# addonv2.net
KiCad netlist of a schematic drawn in EAGLE
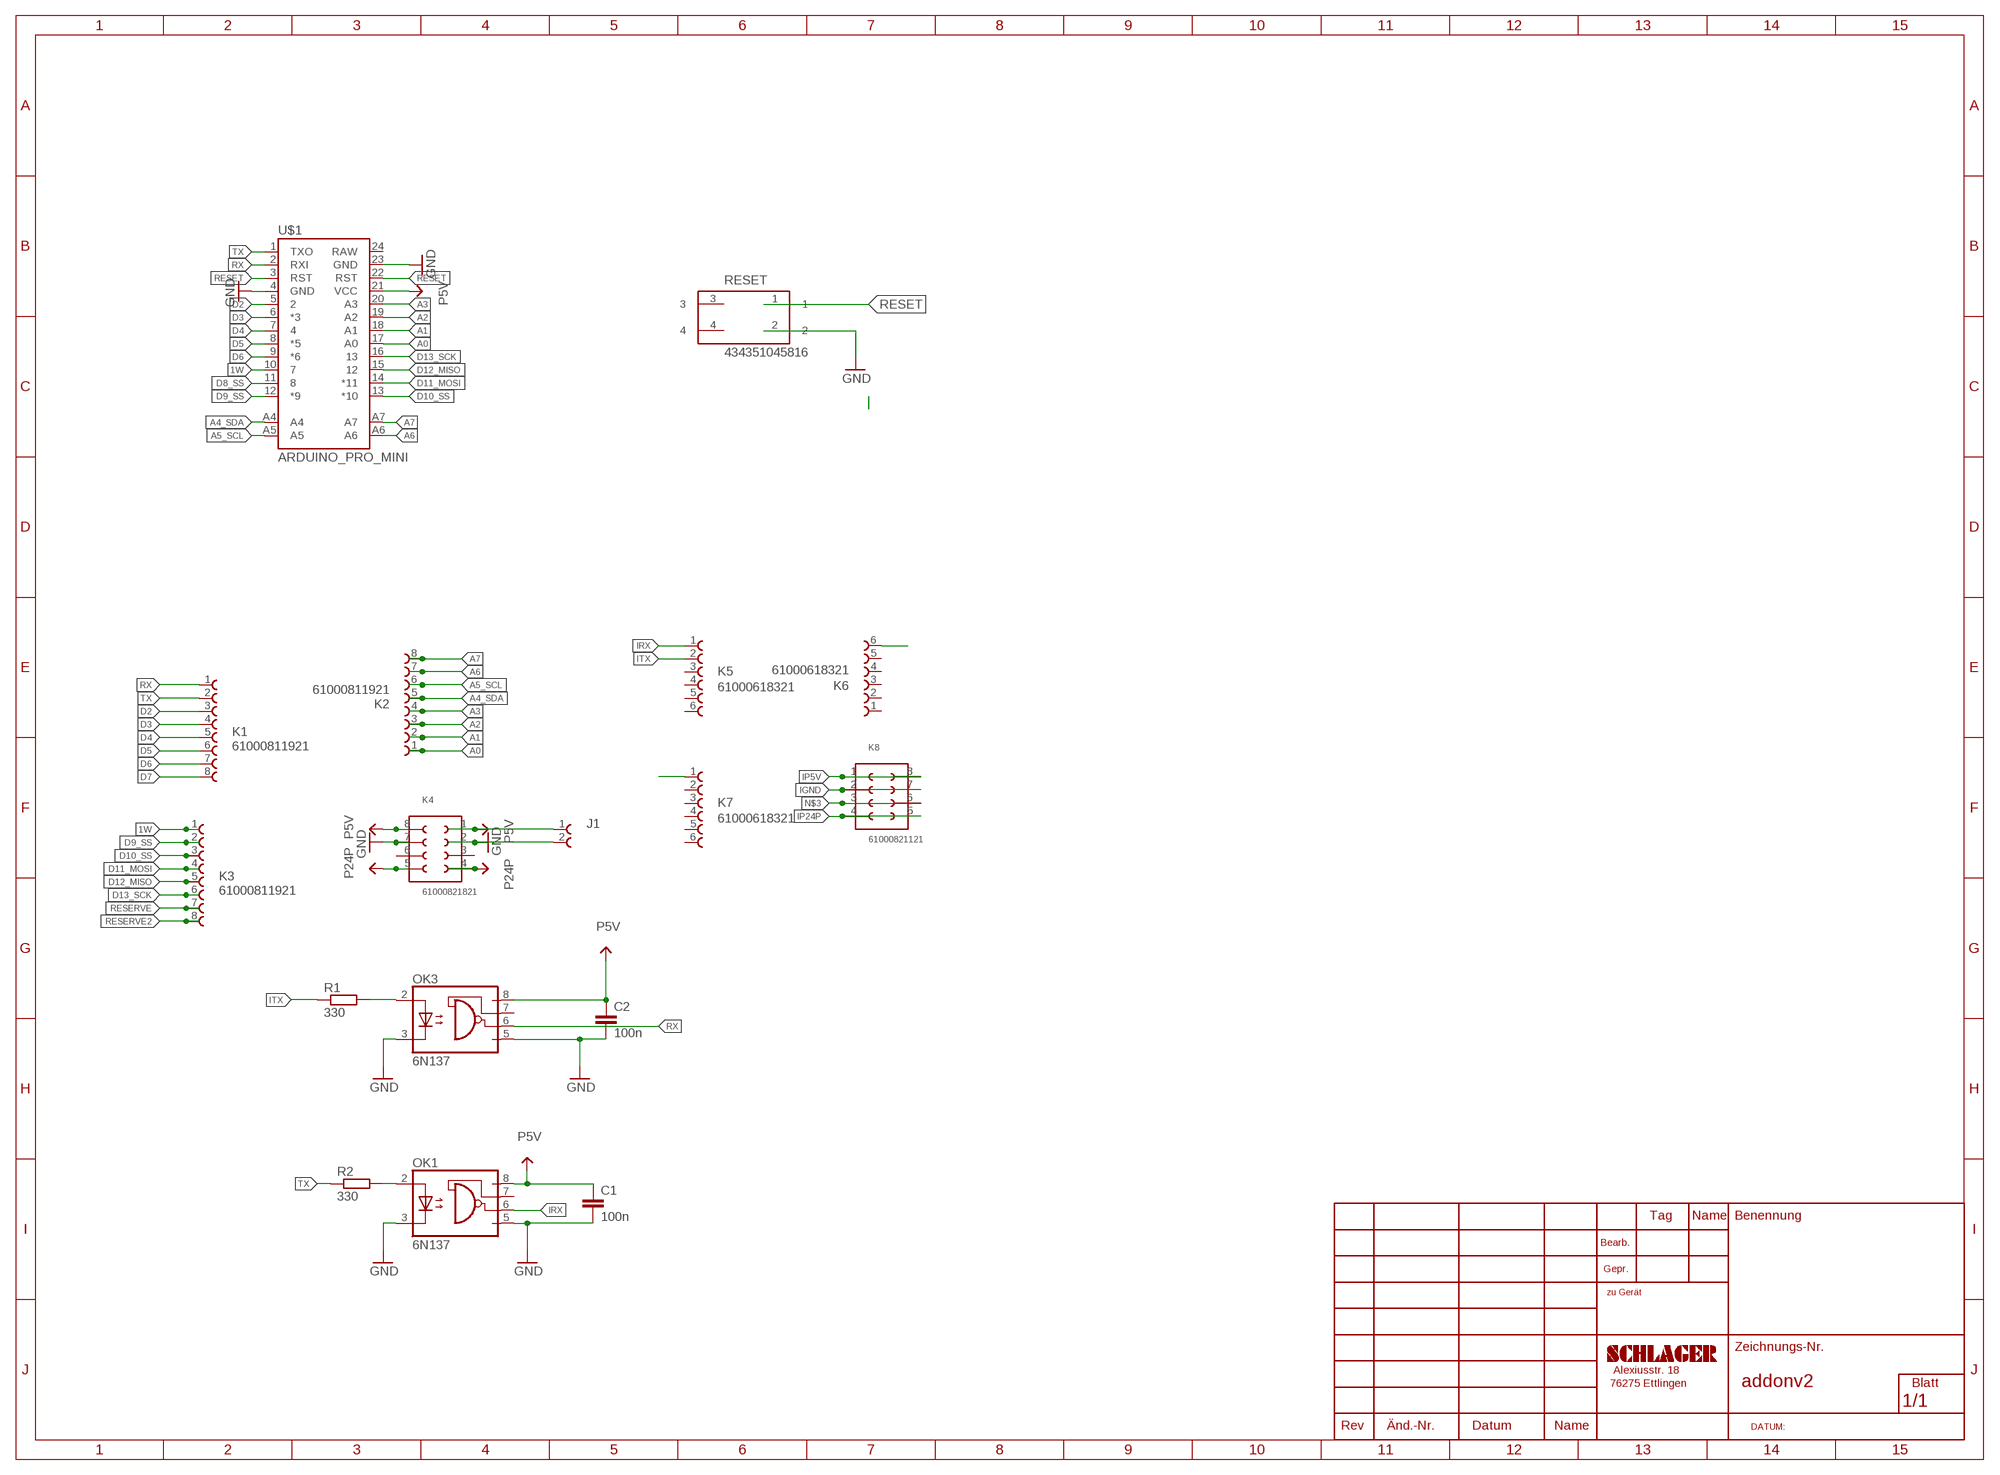
[diagram p0: schematic, sheet 1]

(export (version "E")
  (design (tool "Eeschema 10.0.6"))
  (components
    (comp (ref "C1")
      (value "100n")
      (footprint "eagle-import:C0805")
      (libsource (lib "eagle-import") (part "C-EUC0805"))
    )
    (comp (ref "C2")
      (value "100n")
      (footprint "eagle-import:C0805")
      (libsource (lib "eagle-import") (part "C-EUC0805"))
    )
    (comp (ref "J1")
      (value "691322310002")
      (footprint "eagle-import:691322310002")
      (libsource (lib "eagle-import") (part "691322310002"))
    )
    (comp (ref "K1")
      (value "61000811921")
      (footprint "eagle-import:61000811921")
      (libsource (lib "eagle-import") (part "61000811921"))
    )
    (comp (ref "K2")
      (value "61000811921")
      (footprint "eagle-import:61000811921")
      (libsource (lib "eagle-import") (part "61000811921"))
    )
    (comp (ref "K3")
      (value "61000811921")
      (footprint "eagle-import:61000811921")
      (libsource (lib "eagle-import") (part "61000811921"))
    )
    (comp (ref "K4")
      (value "61000821821")
      (footprint "eagle-import:61000821821")
      (libsource (lib "eagle-import") (part "61000821821"))
    )
    (comp (ref "K5")
      (value "61000618321")
      (footprint "eagle-import:61000618321")
      (libsource (lib "eagle-import") (part "61000618321"))
    )
    (comp (ref "K6")
      (value "61000618321")
      (footprint "eagle-import:61000618321")
      (libsource (lib "eagle-import") (part "61000618321"))
    )
    (comp (ref "K7")
      (value "61000618321")
      (footprint "eagle-import:61000618321")
      (libsource (lib "eagle-import") (part "61000618321"))
    )
    (comp (ref "K8")
      (value "61000821121")
      (footprint "eagle-import:61000821121")
      (libsource (lib "eagle-import") (part "61000821121"))
    )
    (comp (ref "OK1")
      (value "6N137")
      (footprint "eagle-import:DIL08")
      (libsource (lib "eagle-import") (part "6N137"))
    )
    (comp (ref "OK3")
      (value "6N137")
      (footprint "eagle-import:DIL08")
      (libsource (lib "eagle-import") (part "6N137"))
    )
    (comp (ref "R1")
      (value "330")
      (footprint "eagle-import:R0805")
      (libsource (lib "eagle-import") (part "R-EU_R0805"))
    )
    (comp (ref "R2")
      (value "330")
      (footprint "eagle-import:R0805")
      (libsource (lib "eagle-import") (part "R-EU_R0805"))
    )
    (comp (ref "RESET")
      (value "434351045816")
      (footprint "eagle-import:434351045816")
      (libsource (lib "eagle-import") (part "434351045816"))
    )
    (comp (ref "U$1")
      (value "ARDUINO_PRO_MINI")
      (footprint "eagle-import:ARDUINO_PRO_MINI")
      (libsource (lib "eagle-import") (part "ARDUINO_PRO_MINI"))
    )
  )
  (nets
    (net (code "1") (name "1W") (class "Default")
      (node (ref "K3") (pin "1") (pinfunction "1_1") (pintype "passive"))
      (node (ref "U$1") (pin "10") (pinfunction "7_10") (pintype "bidirectional"))
    )
    (net (code "2") (name "A0") (class "Default")
      (node (ref "K2") (pin "1") (pinfunction "1_1") (pintype "passive"))
      (node (ref "U$1") (pin "17") (pinfunction "A0_17") (pintype "bidirectional"))
    )
    (net (code "3") (name "A1") (class "Default")
      (node (ref "K2") (pin "2") (pinfunction "2_2") (pintype "passive"))
      (node (ref "U$1") (pin "18") (pinfunction "A1_18") (pintype "bidirectional"))
    )
    (net (code "4") (name "A2") (class "Default")
      (node (ref "K2") (pin "3") (pinfunction "3_3") (pintype "passive"))
      (node (ref "U$1") (pin "19") (pinfunction "A2_19") (pintype "bidirectional"))
    )
    (net (code "5") (name "A3") (class "Default")
      (node (ref "K2") (pin "4") (pinfunction "4_4") (pintype "passive"))
      (node (ref "U$1") (pin "20") (pinfunction "A3_20") (pintype "bidirectional"))
    )
    (net (code "6") (name "A4_SDA") (class "Default")
      (node (ref "K2") (pin "5") (pinfunction "5_5") (pintype "passive"))
      (node (ref "U$1") (pin "A4") (pinfunction "A4_A4") (pintype "bidirectional"))
    )
    (net (code "7") (name "A5_SCL") (class "Default")
      (node (ref "K2") (pin "6") (pinfunction "6_6") (pintype "passive"))
      (node (ref "U$1") (pin "A5") (pinfunction "A5_A5") (pintype "bidirectional"))
    )
    (net (code "8") (name "A6") (class "Default")
      (node (ref "K2") (pin "7") (pinfunction "7_7") (pintype "passive"))
      (node (ref "U$1") (pin "A6") (pinfunction "A6_A6") (pintype "bidirectional"))
    )
    (net (code "9") (name "A7") (class "Default")
      (node (ref "K2") (pin "8") (pinfunction "8_8") (pintype "passive"))
      (node (ref "U$1") (pin "A7") (pinfunction "A7_A7") (pintype "bidirectional"))
    )
    (net (code "10") (name "D2") (class "Default")
      (node (ref "K1") (pin "3") (pinfunction "3_3") (pintype "passive"))
      (node (ref "U$1") (pin "5") (pinfunction "2_5") (pintype "bidirectional"))
    )
    (net (code "11") (name "D3") (class "Default")
      (node (ref "K1") (pin "4") (pinfunction "4_4") (pintype "passive"))
      (node (ref "U$1") (pin "6") (pinfunction "*3_6") (pintype "bidirectional"))
    )
    (net (code "12") (name "D4") (class "Default")
      (node (ref "K1") (pin "5") (pinfunction "5_5") (pintype "passive"))
      (node (ref "U$1") (pin "7") (pinfunction "4_7") (pintype "bidirectional"))
    )
    (net (code "13") (name "D5") (class "Default")
      (node (ref "K1") (pin "6") (pinfunction "6_6") (pintype "passive"))
      (node (ref "U$1") (pin "8") (pinfunction "*5_8") (pintype "bidirectional"))
    )
    (net (code "14") (name "D6") (class "Default")
      (node (ref "K1") (pin "7") (pinfunction "7_7") (pintype "passive"))
      (node (ref "U$1") (pin "9") (pinfunction "*6_9") (pintype "bidirectional"))
    )
    (net (code "15") (name "D7") (class "Default")
      (node (ref "K1") (pin "8") (pinfunction "8_8") (pintype "passive"))
    )
    (net (code "16") (name "D8_SS") (class "Default")
      (node (ref "U$1") (pin "11") (pinfunction "8_11") (pintype "bidirectional"))
    )
    (net (code "17") (name "D9_SS") (class "Default")
      (node (ref "K3") (pin "2") (pinfunction "2_2") (pintype "passive"))
      (node (ref "U$1") (pin "12") (pinfunction "*9_12") (pintype "bidirectional"))
    )
    (net (code "18") (name "D10_SS") (class "Default")
      (node (ref "K3") (pin "3") (pinfunction "3_3") (pintype "passive"))
      (node (ref "U$1") (pin "13") (pinfunction "*10_13") (pintype "bidirectional"))
    )
    (net (code "19") (name "D11_MOSI") (class "Default")
      (node (ref "K3") (pin "4") (pinfunction "4_4") (pintype "passive"))
      (node (ref "U$1") (pin "14") (pinfunction "*11_14") (pintype "bidirectional"))
    )
    (net (code "20") (name "D12_MISO") (class "Default")
      (node (ref "K3") (pin "5") (pinfunction "5_5") (pintype "passive"))
      (node (ref "U$1") (pin "15") (pinfunction "12_15") (pintype "bidirectional"))
    )
    (net (code "21") (name "D13_SCK") (class "Default")
      (node (ref "K3") (pin "6") (pinfunction "6_6") (pintype "passive"))
      (node (ref "U$1") (pin "16") (pinfunction "13_16") (pintype "bidirectional"))
    )
    (net (code "22") (name "GND") (class "Default")
      (node (ref "C1") (pin "2") (pinfunction "2_2") (pintype "passive"))
      (node (ref "C2") (pin "2") (pinfunction "2_2") (pintype "passive"))
      (node (ref "J1") (pin "2") (pinfunction "2_2") (pintype "passive"))
      (node (ref "K4") (pin "2") (pinfunction "2_2") (pintype "passive"))
      (node (ref "K4") (pin "7") (pinfunction "7_7") (pintype "passive"))
      (node (ref "OK1") (pin "3") (pinfunction "C_3") (pintype "passive"))
      (node (ref "OK1") (pin "5") (pinfunction "GND_5") (pintype "passive"))
      (node (ref "OK3") (pin "3") (pinfunction "C_3") (pintype "passive"))
      (node (ref "OK3") (pin "5") (pinfunction "GND_5") (pintype "passive"))
      (node (ref "RESET") (pin "2") (pinfunction "2_2") (pintype "bidirectional"))
      (node (ref "U$1") (pin "23") (pinfunction "GND_23") (pintype "bidirectional"))
      (node (ref "U$1") (pin "4") (pinfunction "GND_4") (pintype "bidirectional"))
    )
    (net (code "23") (name "IGND") (class "Default")
      (node (ref "K8") (pin "2") (pinfunction "2_2") (pintype "passive"))
      (node (ref "K8") (pin "7") (pinfunction "7_7") (pintype "passive"))
    )
    (net (code "24") (name "IP5V") (class "Default")
      (node (ref "K8") (pin "1") (pinfunction "1_1") (pintype "passive"))
      (node (ref "K8") (pin "8") (pinfunction "8_8") (pintype "passive"))
    )
    (net (code "25") (name "IP24P") (class "Default")
      (node (ref "K8") (pin "4") (pinfunction "4_4") (pintype "passive"))
      (node (ref "K8") (pin "5") (pinfunction "5_5") (pintype "passive"))
    )
    (net (code "26") (name "IRX") (class "Default")
      (node (ref "K5") (pin "1") (pinfunction "1_1") (pintype "passive"))
      (node (ref "OK1") (pin "6") (pinfunction "VO_6") (pintype "passive"))
    )
    (net (code "27") (name "ITX") (class "Default")
      (node (ref "K5") (pin "2") (pinfunction "2_2") (pintype "passive"))
      (node (ref "R1") (pin "1") (pinfunction "1_1") (pintype "passive"))
    )
    (net (code "28") (name "N$3") (class "Default")
      (node (ref "K8") (pin "3") (pinfunction "3_3") (pintype "passive"))
      (node (ref "K8") (pin "6") (pinfunction "6_6") (pintype "passive"))
    )
    (net (code "29") (name "Net-(OK1-A)") (class "Default")
      (node (ref "OK1") (pin "2") (pinfunction "A_2") (pintype "passive"))
      (node (ref "R2") (pin "2") (pinfunction "2_2") (pintype "passive"))
    )
    (net (code "30") (name "Net-(OK3-A)") (class "Default")
      (node (ref "OK3") (pin "2") (pinfunction "A_2") (pintype "passive"))
      (node (ref "R1") (pin "2") (pinfunction "2_2") (pintype "passive"))
    )
    (net (code "31") (name "P5V") (class "Default")
      (node (ref "C1") (pin "1") (pinfunction "1_1") (pintype "passive"))
      (node (ref "C2") (pin "1") (pinfunction "1_1") (pintype "passive"))
      (node (ref "J1") (pin "1") (pinfunction "1_1") (pintype "passive"))
      (node (ref "K4") (pin "1") (pinfunction "1_1") (pintype "passive"))
      (node (ref "K4") (pin "8") (pinfunction "8_8") (pintype "passive"))
      (node (ref "OK1") (pin "8") (pinfunction "VCC_8") (pintype "passive"))
      (node (ref "OK3") (pin "8") (pinfunction "VCC_8") (pintype "passive"))
      (node (ref "U$1") (pin "21") (pinfunction "VCC_21") (pintype "bidirectional"))
    )
    (net (code "32") (name "P24P") (class "Default")
      (node (ref "K4") (pin "4") (pinfunction "4_4") (pintype "passive"))
      (node (ref "K4") (pin "5") (pinfunction "5_5") (pintype "passive"))
    )
    (net (code "33") (name "RESERVE") (class "Default")
      (node (ref "K3") (pin "7") (pinfunction "7_7") (pintype "passive"))
    )
    (net (code "34") (name "RESERVE2") (class "Default")
      (node (ref "K3") (pin "8") (pinfunction "8_8") (pintype "passive"))
    )
    (net (code "35") (name "RESET") (class "Default")
      (node (ref "RESET") (pin "1") (pinfunction "1_1") (pintype "bidirectional"))
      (node (ref "U$1") (pin "22") (pinfunction "RST_22") (pintype "bidirectional"))
      (node (ref "U$1") (pin "3") (pinfunction "RST_3") (pintype "bidirectional"))
    )
    (net (code "36") (name "RX") (class "Default")
      (node (ref "K1") (pin "1") (pinfunction "1_1") (pintype "passive"))
      (node (ref "OK3") (pin "6") (pinfunction "VO_6") (pintype "passive"))
      (node (ref "U$1") (pin "2") (pinfunction "RXI_2") (pintype "bidirectional"))
    )
    (net (code "37") (name "TX") (class "Default")
      (node (ref "K1") (pin "2") (pinfunction "2_2") (pintype "passive"))
      (node (ref "R2") (pin "1") (pinfunction "1_1") (pintype "passive"))
      (node (ref "U$1") (pin "1") (pinfunction "TXO_1") (pintype "bidirectional"))
    )
    (net (code "38") (name "unconnected-(K4-Pad3)") (class "Default")
      (node (ref "K4") (pin "3") (pinfunction "3_3") (pintype "passive"))
    )
    (net (code "39") (name "unconnected-(K4-Pad6)") (class "Default")
      (node (ref "K4") (pin "6") (pinfunction "6_6") (pintype "passive"))
    )
    (net (code "40") (name "unconnected-(K5-Pad3)") (class "Default")
      (node (ref "K5") (pin "3") (pinfunction "3_3") (pintype "passive"))
    )
    (net (code "41") (name "unconnected-(K5-Pad4)") (class "Default")
      (node (ref "K5") (pin "4") (pinfunction "4_4") (pintype "passive"))
    )
    (net (code "42") (name "unconnected-(K5-Pad5)") (class "Default")
      (node (ref "K5") (pin "5") (pinfunction "5_5") (pintype "passive"))
    )
    (net (code "43") (name "unconnected-(K5-Pad6)") (class "Default")
      (node (ref "K5") (pin "6") (pinfunction "6_6") (pintype "passive"))
    )
    (net (code "44") (name "unconnected-(K6-Pad1)") (class "Default")
      (node (ref "K6") (pin "1") (pinfunction "1_1") (pintype "passive"))
    )
    (net (code "45") (name "unconnected-(K6-Pad2)") (class "Default")
      (node (ref "K6") (pin "2") (pinfunction "2_2") (pintype "passive"))
    )
    (net (code "46") (name "unconnected-(K6-Pad3)") (class "Default")
      (node (ref "K6") (pin "3") (pinfunction "3_3") (pintype "passive"))
    )
    (net (code "47") (name "unconnected-(K6-Pad4)") (class "Default")
      (node (ref "K6") (pin "4") (pinfunction "4_4") (pintype "passive"))
    )
    (net (code "48") (name "unconnected-(K6-Pad5)") (class "Default")
      (node (ref "K6") (pin "5") (pinfunction "5_5") (pintype "passive"))
    )
    (net (code "49") (name "unconnected-(K6-Pad6)") (class "Default")
      (node (ref "K6") (pin "6") (pinfunction "6_6") (pintype "passive"))
    )
    (net (code "50") (name "unconnected-(K7-Pad1)") (class "Default")
      (node (ref "K7") (pin "1") (pinfunction "1_1") (pintype "passive"))
    )
    (net (code "51") (name "unconnected-(K7-Pad2)") (class "Default")
      (node (ref "K7") (pin "2") (pinfunction "2_2") (pintype "passive"))
    )
    (net (code "52") (name "unconnected-(K7-Pad3)") (class "Default")
      (node (ref "K7") (pin "3") (pinfunction "3_3") (pintype "passive"))
    )
    (net (code "53") (name "unconnected-(K7-Pad4)") (class "Default")
      (node (ref "K7") (pin "4") (pinfunction "4_4") (pintype "passive"))
    )
    (net (code "54") (name "unconnected-(K7-Pad5)") (class "Default")
      (node (ref "K7") (pin "5") (pinfunction "5_5") (pintype "passive"))
    )
    (net (code "55") (name "unconnected-(K7-Pad6)") (class "Default")
      (node (ref "K7") (pin "6") (pinfunction "6_6") (pintype "passive"))
    )
    (net (code "56") (name "unconnected-(OK1-VE-Pad7)") (class "Default")
      (node (ref "OK1") (pin "7") (pinfunction "VE_7") (pintype "passive"))
    )
    (net (code "57") (name "unconnected-(OK3-VE-Pad7)") (class "Default")
      (node (ref "OK3") (pin "7") (pinfunction "VE_7") (pintype "passive"))
    )
    (net (code "58") (name "unconnected-(RESET-Pad3)") (class "Default")
      (node (ref "RESET") (pin "3") (pinfunction "3_3") (pintype "bidirectional"))
    )
    (net (code "59") (name "unconnected-(RESET-Pad4)") (class "Default")
      (node (ref "RESET") (pin "4") (pinfunction "4_4") (pintype "bidirectional"))
    )
    (net (code "60") (name "unconnected-(U$1-RAW-Pad24)") (class "Default")
      (node (ref "U$1") (pin "24") (pinfunction "RAW_24") (pintype "bidirectional"))
    )
  )
)
